# Lab2.net
KiCad netlist of a schematic drawn in EAGLE
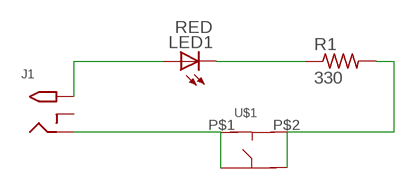
[diagram p0: schematic, sheet 1]

(export (version "E")
  (design (tool "Eeschema 10.0.6"))
  (components
    (comp (ref "J1")
      (value "2.1MMJACKTHM")
      (footprint "eagle-import:PJ-102A")
      (libsource (lib "eagle-import") (part "2.1MMJACKTHM"))
    )
    (comp (ref "LED1")
      (value "RED")
      (footprint "eagle-import:LED5MM")
      (libsource (lib "eagle-import") (part "LED5MM"))
    )
    (comp (ref "R1")
      (value "330")
      (footprint "eagle-import:RESAD1160W55L680D260_HS")
      (libsource (lib "eagle-import") (part "RESISTORTH-1/4W-CARBON"))
    )
    (comp (ref "U$1")
      (value "BUTTON-TACTILE-SQUARE")
      (footprint "eagle-import:BUTTON-TACTILE-SQUARE")
      (libsource (lib "eagle-import") (part "BUTTON-TACTILE-SQUARE"))
    )
  )
  (nets
    (net (code "1") (name "Net-(J1-PadTIP)") (class "Default")
      (node (ref "J1") (pin "TIP") (pinfunction "TIP_TIP") (pintype "bidirectional"))
      (node (ref "LED1") (pin "A") (pinfunction "A_A") (pintype "passive"))
    )
    (net (code "2") (name "Net-(LED1-C)") (class "Default")
      (node (ref "LED1") (pin "K") (pinfunction "C_K") (pintype "passive"))
      (node (ref "R1") (pin "1") (pinfunction "1_1") (pintype "passive"))
    )
    (net (code "3") (name "unconnected-(J1-PadRING)") (class "Default")
      (node (ref "J1") (pin "RING") (pinfunction "RING_RING") (pintype "bidirectional"))
    )
    (net (code "4") (name "unconnected-(J1-PadRING_SW)") (class "Default")
      (node (ref "J1") (pin "RING_SW") (pinfunction "RING_SW_RING_SW") (pintype "bidirectional"))
    )
    (net (code "5") (name "unconnected-(R1-Pad2)") (class "Default")
      (node (ref "R1") (pin "2") (pinfunction "2_2") (pintype "passive"))
    )
    (net (code "6") (name "unconnected-(U$1-PadP$1)") (class "Default")
      (node (ref "U$1") (pin "P$1") (pinfunction "P$1_P$1") (pintype "bidirectional"))
    )
    (net (code "7") (name "unconnected-(U$1-PadP$2)") (class "Default")
      (node (ref "U$1") (pin "P$2") (pinfunction "P$2_P$2") (pintype "bidirectional"))
    )
    (net (code "8") (name "unconnected-(U$1-PadP$3)") (class "Default")
      (node (ref "U$1") (pin "P$3") (pinfunction "P$3_P$3") (pintype "bidirectional"))
    )
    (net (code "9") (name "unconnected-(U$1-PadP$4)") (class "Default")
      (node (ref "U$1") (pin "P$4") (pinfunction "P$4_P$4") (pintype "bidirectional"))
    )
  )
)
